# input-power.net
KiCad netlist of a schematic drawn in EAGLE
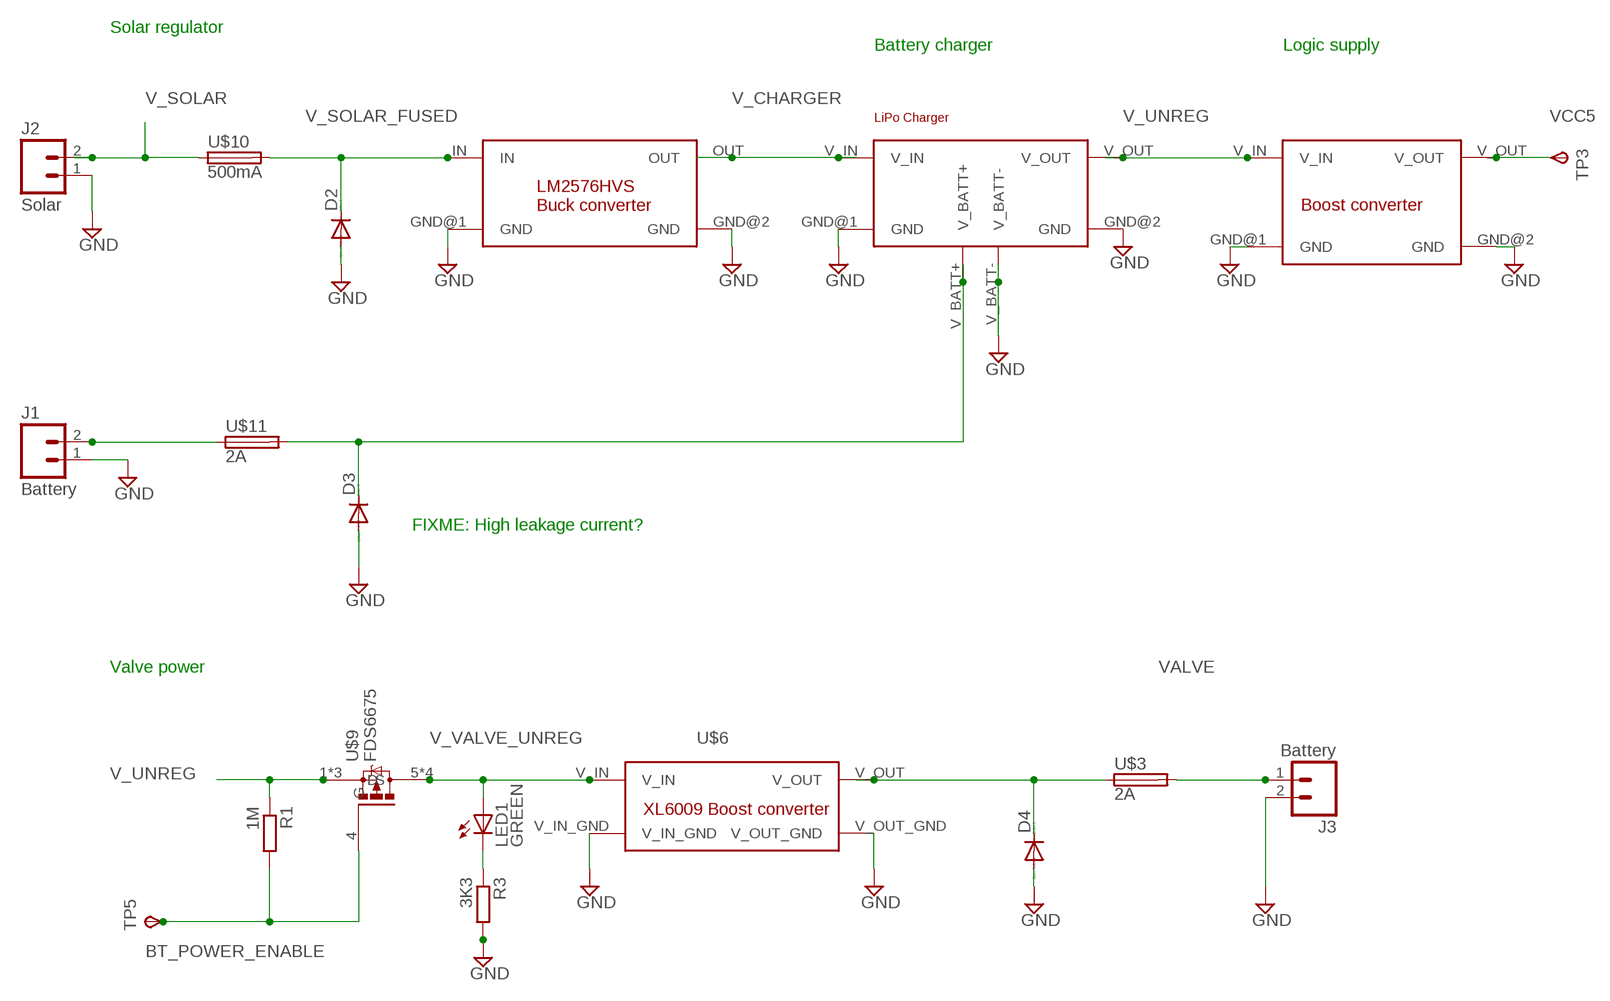
[diagram p0: schematic, sheet 1]

(export (version "E")
  (design (tool "Eeschema 10.0.6"))
  (components
    (comp (ref "D2")
      (value "DIODE-SMB")
      (footprint "eagle-import:SMB")
      (libsource (lib "eagle-import") (part "DIODE-SMB"))
    )
    (comp (ref "D3")
      (value "DIODE-SMB")
      (footprint "eagle-import:SMB")
      (libsource (lib "eagle-import") (part "DIODE-SMB"))
    )
    (comp (ref "D4")
      (value "DIODE-SMB")
      (footprint "eagle-import:SMB")
      (libsource (lib "eagle-import") (part "DIODE-SMB"))
    )
    (comp (ref "J1")
      (value "Battery")
      (footprint "eagle-import:1X02_LONGPADS")
      (libsource (lib "eagle-import") (part "M02PTH3"))
    )
    (comp (ref "J2")
      (value "Solar")
      (footprint "eagle-import:1X02_LONGPADS")
      (libsource (lib "eagle-import") (part "M02PTH3"))
    )
    (comp (ref "J3")
      (value "Battery")
      (footprint "eagle-import:1X02_LONGPADS")
      (libsource (lib "eagle-import") (part "M02PTH3"))
    )
    (comp (ref "LED1")
      (value "GREEN")
      (footprint "eagle-import:LED3MM")
      (libsource (lib "eagle-import") (part "LED3MM"))
    )
    (comp (ref "R1")
      (value "1M")
      (footprint "eagle-import:R0805")
      (libsource (lib "eagle-import") (part "R-EU_R0805"))
    )
    (comp (ref "R3")
      (value "3K3")
      (footprint "eagle-import:R0805")
      (libsource (lib "eagle-import") (part "R-EU_R0805"))
    )
    (comp (ref "TP3")
      (value "TPSB1,27")
      (footprint "eagle-import:B1,27")
      (libsource (lib "eagle-import") (part "TPSB1,27"))
    )
    (comp (ref "TP5")
      (value "TPSB1,27")
      (footprint "eagle-import:B1,27")
      (libsource (lib "eagle-import") (part "TPSB1,27"))
    )
    (comp (ref "U$2")
      (value "BATTERY_CHARGER")
      (footprint "eagle-import:BATTERY_CHARGER")
      (libsource (lib "eagle-import") (part "BATTERY_CHARGER"))
    )
    (comp (ref "U$3")
      (value "2A")
      (footprint "eagle-import:MF-SMDF050")
      (libsource (lib "eagle-import") (part "MF-SMDF150"))
    )
    (comp (ref "U$5")
      (value "QSKJ_BOOST_MODULE")
      (footprint "eagle-import:QSKJ_BOOST_MODULE")
      (libsource (lib "eagle-import") (part "QSKJ_BOOST_MODULE"))
    )
    (comp (ref "U$6")
      (value "XL6009_BOOST_MODULE")
      (footprint "eagle-import:XL6009_BOOST_MODULE")
      (libsource (lib "eagle-import") (part "XL6009_BOOST_MODULE"))
    )
    (comp (ref "U$8")
      (value "LM2576HVS_BUCK_MODULE")
      (footprint "eagle-import:LM2576HVS_BUCK_MODULE")
      (libsource (lib "eagle-import") (part "LM2576HVS_BUCK_MODULE"))
    )
    (comp (ref "U$9")
      (value "FDS6675")
      (footprint "eagle-import:SO08")
      (libsource (lib "eagle-import") (part "FDS6675"))
    )
    (comp (ref "U$10")
      (value "500mA")
      (footprint "eagle-import:MF-SMDF050")
      (libsource (lib "eagle-import") (part "MF-SMDF150"))
    )
    (comp (ref "U$11")
      (value "2A")
      (footprint "eagle-import:MF-SMDF050")
      (libsource (lib "eagle-import") (part "MF-SMDF150"))
    )
  )
  (nets
    (net (code "1") (name "/BT_POWER_ENABLE") (class "Default")
      (node (ref "R1") (pin "2") (pinfunction "2_2") (pintype "passive"))
      (node (ref "TP5") (pin "TP") (pinfunction "PP_TP") (pintype "input"))
      (node (ref "U$9") (pin "4") (pinfunction "G_4") (pintype "bidirectional"))
    )
    (net (code "2") (name "/VALVE") (class "Default")
      (node (ref "J3") (pin "1") (pinfunction "1_1") (pintype "passive"))
      (node (ref "U$3") (pin "2") (pinfunction "2_2") (pintype "passive"))
    )
    (net (code "3") (name "/VCC5") (class "Default")
      (node (ref "TP3") (pin "TP") (pinfunction "PP_TP") (pintype "input"))
      (node (ref "U$5") (pin "V_OUT") (pinfunction "V_OUT_V_OUT") (pintype "bidirectional"))
    )
    (net (code "4") (name "/V_CHARGER") (class "Default")
      (node (ref "U$2") (pin "V_IN") (pinfunction "V_IN_V_IN") (pintype "bidirectional"))
      (node (ref "U$8") (pin "OUT") (pinfunction "OUT_OUT") (pintype "output"))
    )
    (net (code "5") (name "/V_SOLAR") (class "Default")
      (node (ref "J2") (pin "2") (pinfunction "2_2") (pintype "passive"))
      (node (ref "U$10") (pin "1") (pinfunction "1_1") (pintype "passive"))
    )
    (net (code "6") (name "/V_SOLAR_FUSED") (class "Default")
      (node (ref "D2") (pin "C") (pinfunction "C_C") (pintype "passive"))
      (node (ref "U$10") (pin "2") (pinfunction "2_2") (pintype "passive"))
      (node (ref "U$8") (pin "IN") (pinfunction "IN_IN") (pintype "power_in"))
    )
    (net (code "7") (name "/V_UNREG") (class "Default")
      (node (ref "R1") (pin "1") (pinfunction "1_1") (pintype "passive"))
      (node (ref "U$2") (pin "V_OUT") (pinfunction "V_OUT_V_OUT") (pintype "bidirectional"))
      (node (ref "U$5") (pin "V_IN") (pinfunction "V_IN_V_IN") (pintype "power_in"))
      (node (ref "U$9") (pin "1") (pinfunction "S_1") (pintype "bidirectional"))
      (node (ref "U$9") (pin "2") (pinfunction "S_2") (pintype "bidirectional"))
      (node (ref "U$9") (pin "3") (pinfunction "S_3") (pintype "bidirectional"))
    )
    (net (code "8") (name "/V_VALVE_UNREG") (class "Default")
      (node (ref "LED1") (pin "A") (pinfunction "A_A") (pintype "passive"))
      (node (ref "U$6") (pin "V_IN") (pinfunction "V_IN_V_IN") (pintype "power_in"))
      (node (ref "U$9") (pin "5") (pinfunction "D_5") (pintype "bidirectional"))
      (node (ref "U$9") (pin "6") (pinfunction "D_6") (pintype "bidirectional"))
      (node (ref "U$9") (pin "7") (pinfunction "D_7") (pintype "bidirectional"))
      (node (ref "U$9") (pin "8") (pinfunction "D_8") (pintype "bidirectional"))
    )
    (net (code "9") (name "GND") (class "Default")
      (node (ref "D2") (pin "A") (pinfunction "A_A") (pintype "passive"))
      (node (ref "D3") (pin "A") (pinfunction "A_A") (pintype "passive"))
      (node (ref "D4") (pin "A") (pinfunction "A_A") (pintype "passive"))
      (node (ref "J1") (pin "1") (pinfunction "1_1") (pintype "passive"))
      (node (ref "J2") (pin "1") (pinfunction "1_1") (pintype "passive"))
      (node (ref "J3") (pin "2") (pinfunction "2_2") (pintype "passive"))
      (node (ref "R3") (pin "2") (pinfunction "2_2") (pintype "passive"))
      (node (ref "U$2") (pin "GND@1") (pinfunction "GND_GND@1") (pintype "bidirectional"))
      (node (ref "U$2") (pin "GND@2") (pinfunction "GND_GND@2") (pintype "bidirectional"))
      (node (ref "U$2") (pin "V_BATT-") (pinfunction "V_BATT-_V_BATT-") (pintype "bidirectional"))
      (node (ref "U$5") (pin "GND@1") (pinfunction "GND_GND@1") (pintype "power_in"))
      (node (ref "U$5") (pin "GND@2") (pinfunction "GND_GND@2") (pintype "power_in"))
      (node (ref "U$6") (pin "V_IN_GND") (pinfunction "V_IN_GND_V_IN_GND") (pintype "power_in"))
      (node (ref "U$6") (pin "V_OUT_GND") (pinfunction "V_OUT_GND_V_OUT_GND") (pintype "power_in"))
      (node (ref "U$8") (pin "GND@1") (pinfunction "GND_GND@1") (pintype "power_in"))
      (node (ref "U$8") (pin "GND@2") (pinfunction "GND_GND@2") (pintype "power_in"))
    )
    (net (code "10") (name "Net-(D3-PadC)") (class "Default")
      (node (ref "D3") (pin "C") (pinfunction "C_C") (pintype "passive"))
      (node (ref "U$11") (pin "2") (pinfunction "2_2") (pintype "passive"))
      (node (ref "U$2") (pin "V_BATT+") (pinfunction "V_BATT+_V_BATT+") (pintype "bidirectional"))
    )
    (net (code "11") (name "Net-(D4-PadC)") (class "Default")
      (node (ref "D4") (pin "C") (pinfunction "C_C") (pintype "passive"))
      (node (ref "U$3") (pin "1") (pinfunction "1_1") (pintype "passive"))
      (node (ref "U$6") (pin "V_OUT") (pinfunction "V_OUT_V_OUT") (pintype "output"))
    )
    (net (code "12") (name "Net-(J1-Pad2)") (class "Default")
      (node (ref "J1") (pin "2") (pinfunction "2_2") (pintype "passive"))
      (node (ref "U$11") (pin "1") (pinfunction "1_1") (pintype "passive"))
    )
    (net (code "13") (name "Net-(LED1-C)") (class "Default")
      (node (ref "LED1") (pin "K") (pinfunction "C_K") (pintype "passive"))
      (node (ref "R3") (pin "1") (pinfunction "1_1") (pintype "passive"))
    )
  )
)
